# RTM_Connectors.net
KiCad netlist of a schematic drawn in Altium Designer
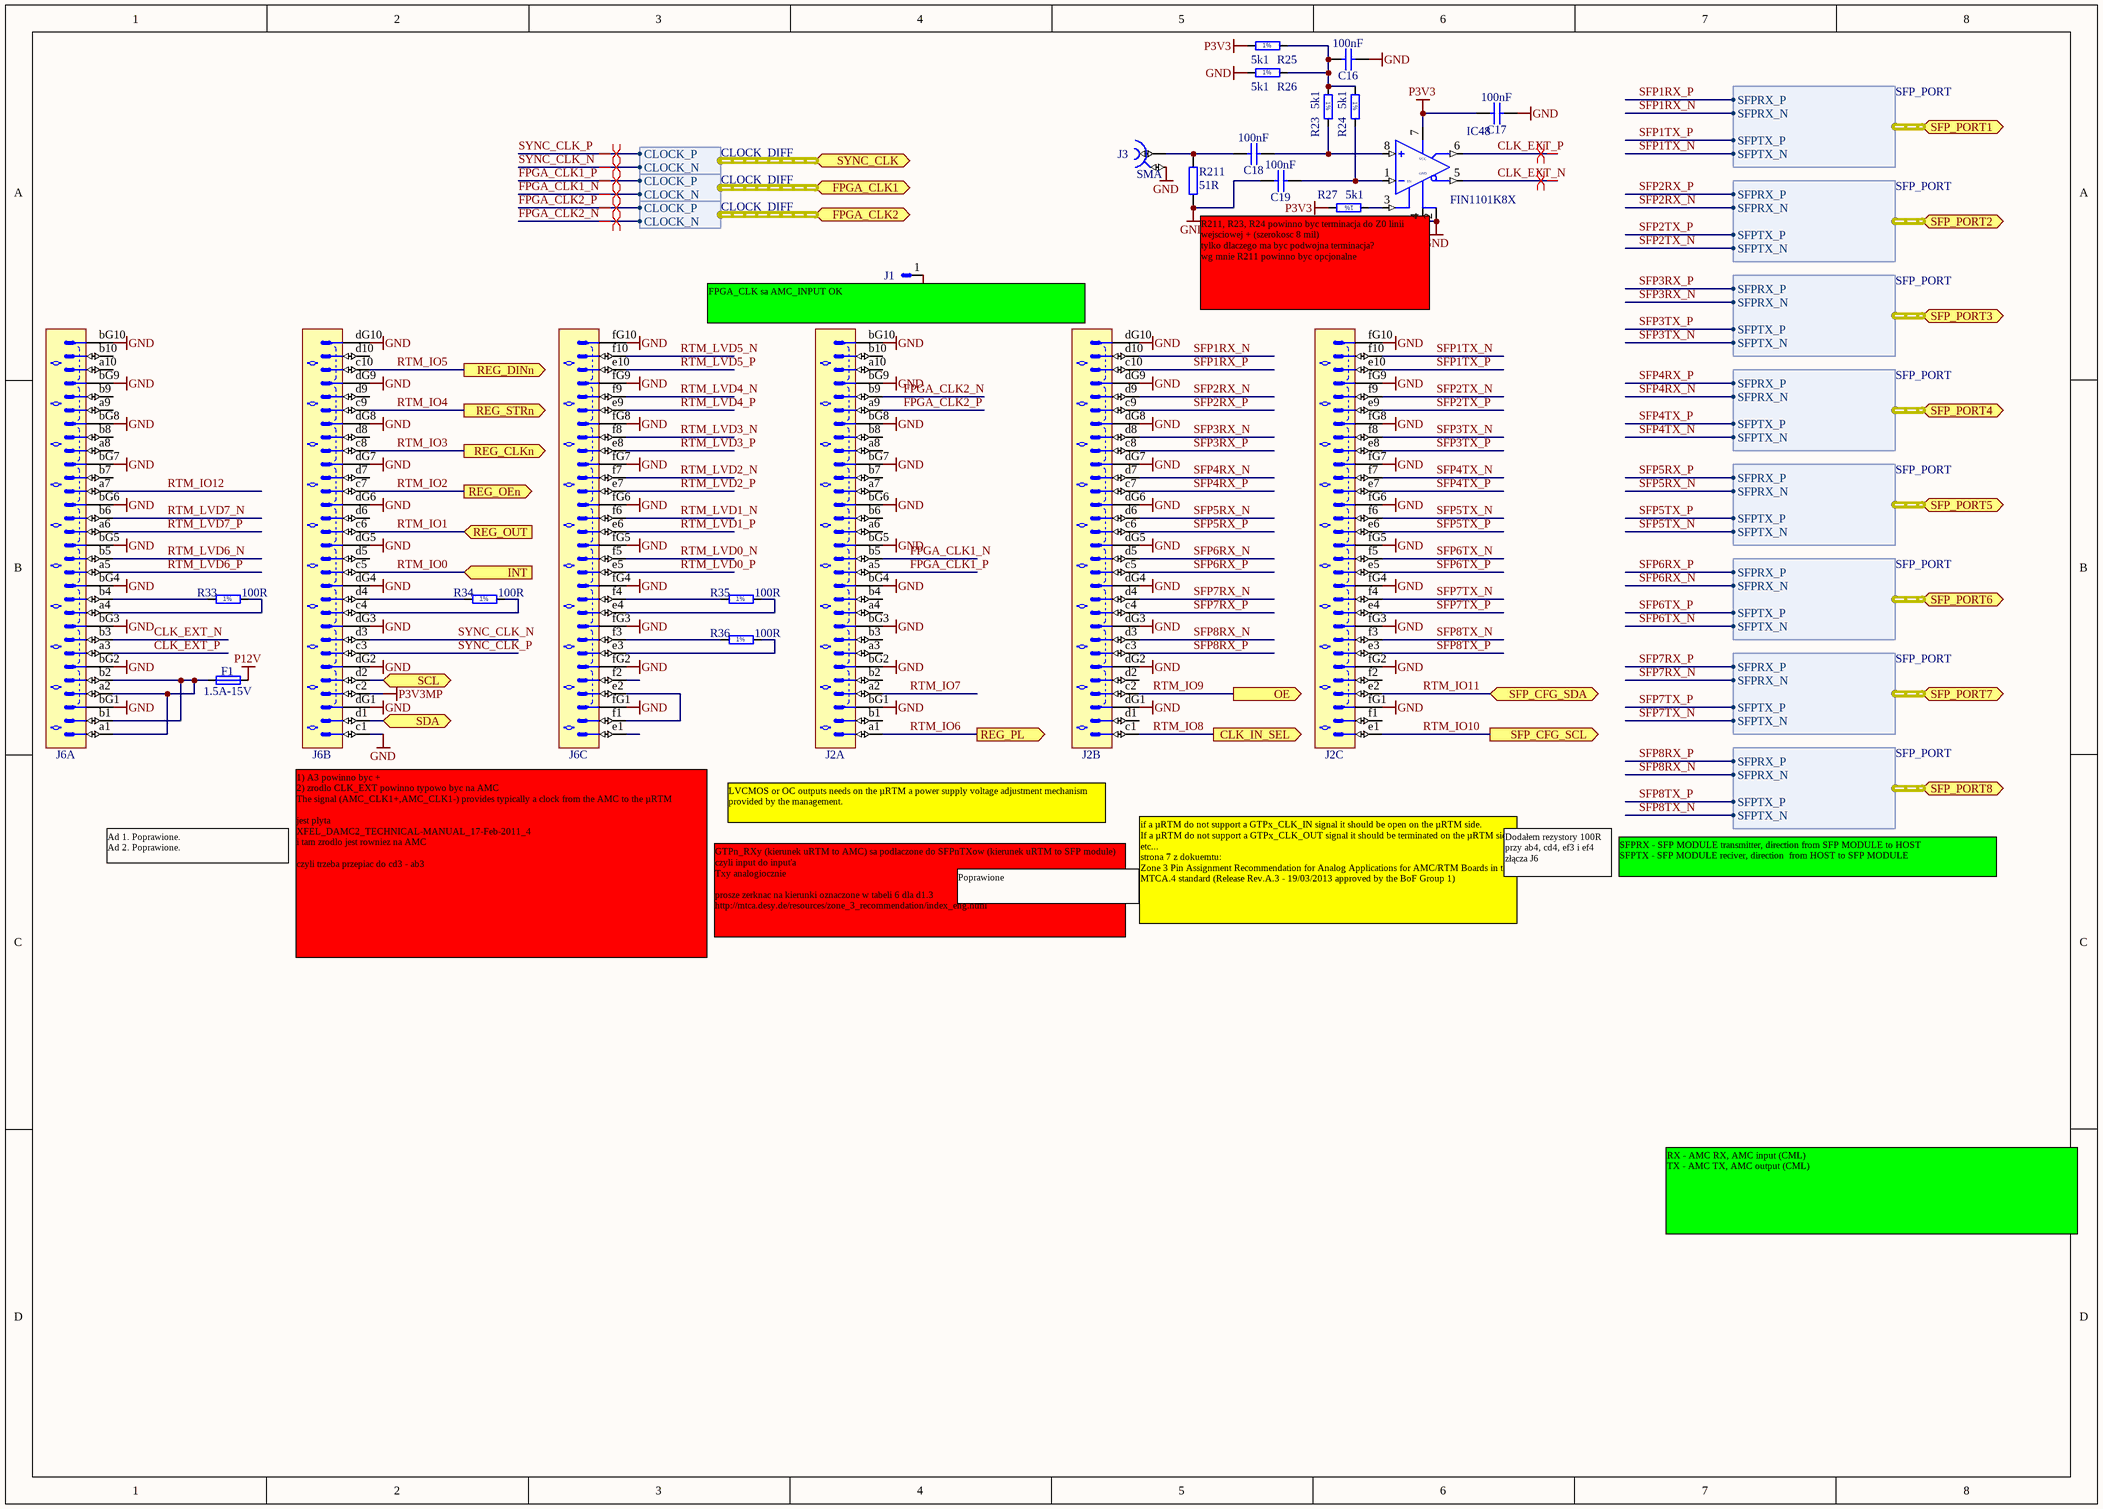
[diagram p0: RTM_Connectors.SchDoc]

(export (version "E")
  (design (tool "Eeschema 10.0.6"))
  (components
    (comp (ref "C16")
      (value "100nF")
      (footprint "CAPC1005X55N")
      (description "Non-polarised capacitor")
      (fields
        (field (name "PART NUMBER") "CC0402_100NF_16V_10%_X7R")
        (field (name "VOLTAGE") "16V")
        (field (name "AUTHOR") "CERN DEM JLC")
      )
      (libsource (lib "Capacitors") (part "Capacitor - non polarized"))
    )
    (comp (ref "C17")
      (value "100nF")
      (footprint "CAPC1005X55N")
      (description "Non-polarised capacitor")
      (fields
        (field (name "PART NUMBER") "CC0402_100NF_16V_10%_X7R")
        (field (name "VOLTAGE") "16V")
        (field (name "AUTHOR") "CERN DEM JLC")
      )
      (libsource (lib "Capacitors") (part "Capacitor - non polarized"))
    )
    (comp (ref "C18")
      (value "100nF")
      (footprint "CAPC1005X55N")
      (description "Non-polarised capacitor")
      (fields
        (field (name "PART NUMBER") "CC0402_100NF_16V_10%_X7R")
        (field (name "VOLTAGE") "16V")
        (field (name "AUTHOR") "CERN DEM JLC")
      )
      (libsource (lib "Capacitors") (part "Capacitor - non polarized"))
    )
    (comp (ref "C19")
      (value "100nF")
      (footprint "CAPC1005X55N")
      (description "Non-polarised capacitor")
      (fields
        (field (name "PART NUMBER") "CC0402_100NF_16V_10%_X7R")
        (field (name "VOLTAGE") "16V")
        (field (name "AUTHOR") "CERN DEM JLC")
      )
      (libsource (lib "Capacitors") (part "Capacitor - non polarized"))
    )
    (comp (ref "F1")
      (value "1.5A-15V")
      (footprint "FUSR_TYCO_SMD150F-2")
      (description "Fuse")
      (fields
        (field (name "PART NUMBER") "FUSR_TYCO_SMD150F-2")
        (field (name "MANUFACTURER") "TYCO ELECTRONICS")
        (field (name "AUTHOR") "CERN DEM JLC")
      )
      (libsource (lib "Eletro-mechanical") (part "Fuse"))
    )
    (comp (ref "IC48")
      (value "FIN1101K8X")
      (footprint "US8")
      (description "LVDS TO LVDS repeater3.3V")
      (libsource (lib "AMC_FMC_Carrier") (part "IFC_FIN1101K8X"))
    )
    (comp (ref "J1")
      (value "~")
      (footprint "TYCO_1469265-1")
      (description "Single Pin Male")
      (fields (field (name "PART NUMBER") "TYCO_1469265-1"))
      (libsource (lib "Connectors") (part "Single Pin Male"))
    )
    (comp (ref "J2")
      (value "~")
      (footprint "TYCO_6469183-1")
      (description "Connector 60 ATCA Male 30 Pairs (60 Signals) + 3x10 Ground")
      (fields (field (name "PART NUMBER") "TYCO_6469183-1"))
      (libsource (lib "Connectors") (part "Connector ATCA 60+30 Male"))
    )
    (comp (ref "J3")
      (value "SMA")
      (footprint "HUBER-SUHNER_85 SMA-50-0-101/111 NE")
      (fields
        (field (name "PART NUMBER") "HUBER-SUHNER_85_SMA-50-0-101/111_NE")
        (field (name "MANUFACTURER") "HUBER+SUHNER")
        (field (name "MANUFACTURER PART NUMBER") "85_SMA-50-0-101/111_NE")
        (field (name "AUTHOR") "CERN DEM JLC")
      )
      (libsource (lib "Connectors") (part "Coax_1Female_1Shield"))
    )
    (comp (ref "J6")
      (value "~")
      (footprint "TYCO_6469183-1")
      (description "Connector 60 ATCA Male 30 Pairs (60 Signals) + 3x10 Ground")
      (fields (field (name "PART NUMBER") "TYCO_6469183-1"))
      (libsource (lib "Connectors") (part "Connector ATCA 60+30 Male"))
    )
    (comp (ref "R23")
      (value "5k1")
      (footprint "RESC1608X55N")
      (description "Resistor - 1%")
      (fields
        (field (name "PART NUMBER") "R0603_5K1_1%_0.1W_100PPM")
        (field (name "POWER") "0.1W")
        (field (name "AUTHOR") "CERN DEM JLC")
      )
      (libsource (lib "Resistors") (part "Resistor - 1%"))
    )
    (comp (ref "R24")
      (value "5k1")
      (footprint "RESC1608X55N")
      (description "Resistor - 1%")
      (fields
        (field (name "PART NUMBER") "R0603_5K1_1%_0.1W_100PPM")
        (field (name "POWER") "0.1W")
        (field (name "AUTHOR") "CERN DEM JLC")
      )
      (libsource (lib "Resistors") (part "Resistor - 1%"))
    )
    (comp (ref "R25")
      (value "5k1")
      (footprint "RESC1608X55N")
      (description "Resistor - 1%")
      (fields
        (field (name "PART NUMBER") "R0603_5K1_1%_0.1W_100PPM")
        (field (name "POWER") "0.1W")
        (field (name "AUTHOR") "CERN DEM JLC")
      )
      (libsource (lib "Resistors") (part "Resistor - 1%"))
    )
    (comp (ref "R26")
      (value "5k1")
      (footprint "RESC1608X55N")
      (description "Resistor - 1%")
      (fields
        (field (name "PART NUMBER") "R0603_5K1_1%_0.1W_100PPM")
        (field (name "POWER") "0.1W")
        (field (name "AUTHOR") "CERN DEM JLC")
      )
      (libsource (lib "Resistors") (part "Resistor - 1%"))
    )
    (comp (ref "R27")
      (value "5k1")
      (footprint "RESC1608X55N")
      (description "Resistor - 1%")
      (fields
        (field (name "PART NUMBER") "R0603_5K1_1%_0.1W_100PPM")
        (field (name "POWER") "0.1W")
        (field (name "AUTHOR") "CERN DEM JLC")
      )
      (libsource (lib "Resistors") (part "Resistor - 1%"))
    )
    (comp (ref "R33")
      (value "100R")
      (footprint "RESC1608X55N")
      (description "Resistor - 1%")
      (fields
        (field (name "PART NUMBER") "R0603_5K1_1%_0.1W_100PPM")
        (field (name "POWER") "0.1W")
        (field (name "AUTHOR") "CERN DEM JLC")
      )
      (libsource (lib "Resistors") (part "Resistor - 1%"))
    )
    (comp (ref "R34")
      (value "100R")
      (footprint "RESC1608X55N")
      (description "Resistor - 1%")
      (fields
        (field (name "PART NUMBER") "R0603_5K1_1%_0.1W_100PPM")
        (field (name "POWER") "0.1W")
        (field (name "AUTHOR") "CERN DEM JLC")
      )
      (libsource (lib "Resistors") (part "Resistor - 1%"))
    )
    (comp (ref "R35")
      (value "100R")
      (footprint "RESC1608X55N")
      (description "Resistor - 1%")
      (fields
        (field (name "PART NUMBER") "R0603_5K1_1%_0.1W_100PPM")
        (field (name "POWER") "0.1W")
        (field (name "AUTHOR") "CERN DEM JLC")
      )
      (libsource (lib "Resistors") (part "Resistor - 1%"))
    )
    (comp (ref "R36")
      (value "100R")
      (footprint "RESC1608X55N")
      (description "Resistor - 1%")
      (fields
        (field (name "PART NUMBER") "R0603_5K1_1%_0.1W_100PPM")
        (field (name "POWER") "0.1W")
        (field (name "AUTHOR") "CERN DEM JLC")
      )
      (libsource (lib "Resistors") (part "Resistor - 1%"))
    )
    (comp (ref "R211")
      (value "51R")
      (footprint "0402R")
      (description "SMD Resistor")
      (libsource (lib "LIBRARY_SCH") (part "RES_0402"))
    )
  )
  (nets
    (net (code "3") (name "/CLK_EXT_N") (class "Default")
      (node (ref "IC48") (pin "5") (pinfunction "~{Q}_5") (pintype "output"))
      (node (ref "J6") (pin "b3") (pinfunction "b3_b3") (pintype "bidirectional"))
    )
    (net (code "4") (name "/CLK_EXT_P") (class "Default")
      (node (ref "IC48") (pin "6") (pinfunction "Q_6") (pintype "output"))
      (node (ref "J6") (pin "a3") (pinfunction "a3_a3") (pintype "bidirectional"))
    )
    (net (code "5") (name "/FPGA_CLK1_N") (class "Default")
      (node (ref "J2") (pin "b5") (pinfunction "b5_b5") (pintype "bidirectional"))
    )
    (net (code "6") (name "/FPGA_CLK1_P") (class "Default")
      (node (ref "J2") (pin "a5") (pinfunction "a5_a5") (pintype "bidirectional"))
    )
    (net (code "7") (name "/FPGA_CLK2_N") (class "Default")
      (node (ref "J2") (pin "b9") (pinfunction "b9_b9") (pintype "bidirectional"))
    )
    (net (code "8") (name "/FPGA_CLK2_P") (class "Default")
      (node (ref "J2") (pin "a9") (pinfunction "a9_a9") (pintype "bidirectional"))
    )
    (net (code "9") (name "/RTM_IO0") (class "Default")
      (node (ref "J6") (pin "c5") (pinfunction "c5_c5") (pintype "bidirectional"))
    )
    (net (code "10") (name "/RTM_IO1") (class "Default")
      (node (ref "J6") (pin "c6") (pinfunction "c6_c6") (pintype "bidirectional"))
    )
    (net (code "11") (name "/RTM_IO2") (class "Default")
      (node (ref "J6") (pin "c7") (pinfunction "c7_c7") (pintype "bidirectional"))
    )
    (net (code "12") (name "/RTM_IO3") (class "Default")
      (node (ref "J6") (pin "c8") (pinfunction "c8_c8") (pintype "bidirectional"))
    )
    (net (code "13") (name "/RTM_IO4") (class "Default")
      (node (ref "J6") (pin "c9") (pinfunction "c9_c9") (pintype "bidirectional"))
    )
    (net (code "14") (name "/RTM_IO5") (class "Default")
      (node (ref "J6") (pin "c10") (pinfunction "c10_c10") (pintype "bidirectional"))
    )
    (net (code "15") (name "/RTM_IO6") (class "Default")
      (node (ref "J2") (pin "a1") (pinfunction "a1_a1") (pintype "bidirectional"))
    )
    (net (code "16") (name "/RTM_IO7") (class "Default")
      (node (ref "J2") (pin "a2") (pinfunction "a2_a2") (pintype "bidirectional"))
    )
    (net (code "17") (name "/RTM_IO8") (class "Default")
      (node (ref "J2") (pin "c1") (pinfunction "c1_c1") (pintype "bidirectional"))
    )
    (net (code "18") (name "/RTM_IO9") (class "Default")
      (node (ref "J2") (pin "c2") (pinfunction "c2_c2") (pintype "bidirectional"))
    )
    (net (code "19") (name "/RTM_IO10") (class "Default")
      (node (ref "J2") (pin "e1") (pinfunction "e1_e1") (pintype "bidirectional"))
    )
    (net (code "20") (name "/RTM_IO11") (class "Default")
      (node (ref "J2") (pin "e2") (pinfunction "e2_e2") (pintype "bidirectional"))
    )
    (net (code "21") (name "/RTM_IO12") (class "Default")
      (node (ref "J6") (pin "a7") (pinfunction "a7_a7") (pintype "bidirectional"))
    )
    (net (code "22") (name "/RTM_LVD0_N") (class "Default")
      (node (ref "J6") (pin "f5") (pinfunction "f5_f5") (pintype "bidirectional"))
    )
    (net (code "23") (name "/RTM_LVD0_P") (class "Default")
      (node (ref "J6") (pin "e5") (pinfunction "e5_e5") (pintype "bidirectional"))
    )
    (net (code "24") (name "/RTM_LVD1_N") (class "Default")
      (node (ref "J6") (pin "f6") (pinfunction "f6_f6") (pintype "bidirectional"))
    )
    (net (code "25") (name "/RTM_LVD1_P") (class "Default")
      (node (ref "J6") (pin "e6") (pinfunction "e6_e6") (pintype "bidirectional"))
    )
    (net (code "26") (name "/RTM_LVD2_N") (class "Default")
      (node (ref "J6") (pin "f7") (pinfunction "f7_f7") (pintype "bidirectional"))
    )
    (net (code "27") (name "/RTM_LVD2_P") (class "Default")
      (node (ref "J6") (pin "e7") (pinfunction "e7_e7") (pintype "bidirectional"))
    )
    (net (code "28") (name "/RTM_LVD3_N") (class "Default")
      (node (ref "J6") (pin "f8") (pinfunction "f8_f8") (pintype "bidirectional"))
    )
    (net (code "29") (name "/RTM_LVD3_P") (class "Default")
      (node (ref "J6") (pin "e8") (pinfunction "e8_e8") (pintype "bidirectional"))
    )
    (net (code "30") (name "/RTM_LVD4_N") (class "Default")
      (node (ref "J6") (pin "f9") (pinfunction "f9_f9") (pintype "bidirectional"))
    )
    (net (code "31") (name "/RTM_LVD4_P") (class "Default")
      (node (ref "J6") (pin "e9") (pinfunction "e9_e9") (pintype "bidirectional"))
    )
    (net (code "32") (name "/RTM_LVD5_N") (class "Default")
      (node (ref "J6") (pin "f10") (pinfunction "f10_f10") (pintype "bidirectional"))
    )
    (net (code "33") (name "/RTM_LVD5_P") (class "Default")
      (node (ref "J6") (pin "e10") (pinfunction "e10_e10") (pintype "bidirectional"))
    )
    (net (code "34") (name "/RTM_LVD6_N") (class "Default")
      (node (ref "J6") (pin "b5") (pinfunction "b5_b5") (pintype "bidirectional"))
    )
    (net (code "35") (name "/RTM_LVD6_P") (class "Default")
      (node (ref "J6") (pin "a5") (pinfunction "a5_a5") (pintype "bidirectional"))
    )
    (net (code "36") (name "/RTM_LVD7_N") (class "Default")
      (node (ref "J6") (pin "b6") (pinfunction "b6_b6") (pintype "bidirectional"))
    )
    (net (code "37") (name "/RTM_LVD7_P") (class "Default")
      (node (ref "J6") (pin "a6") (pinfunction "a6_a6") (pintype "bidirectional"))
    )
    (net (code "38") (name "/SCL") (class "Default")
      (node (ref "J6") (pin "d2") (pinfunction "d2_d2") (pintype "bidirectional"))
    )
    (net (code "39") (name "/SDA") (class "Default")
      (node (ref "J6") (pin "d1") (pinfunction "d1_d1") (pintype "bidirectional"))
    )
    (net (code "40") (name "/SFP1RX_N") (class "Default")
      (node (ref "J2") (pin "d10") (pinfunction "d10_d10") (pintype "bidirectional"))
    )
    (net (code "41") (name "/SFP1RX_P") (class "Default")
      (node (ref "J2") (pin "c10") (pinfunction "c10_c10") (pintype "bidirectional"))
    )
    (net (code "42") (name "/SFP1TX_N") (class "Default")
      (node (ref "J2") (pin "f10") (pinfunction "f10_f10") (pintype "bidirectional"))
    )
    (net (code "43") (name "/SFP1TX_P") (class "Default")
      (node (ref "J2") (pin "e10") (pinfunction "e10_e10") (pintype "bidirectional"))
    )
    (net (code "44") (name "/SFP2RX_N") (class "Default")
      (node (ref "J2") (pin "d9") (pinfunction "d9_d9") (pintype "bidirectional"))
    )
    (net (code "45") (name "/SFP2RX_P") (class "Default")
      (node (ref "J2") (pin "c9") (pinfunction "c9_c9") (pintype "bidirectional"))
    )
    (net (code "46") (name "/SFP2TX_N") (class "Default")
      (node (ref "J2") (pin "f9") (pinfunction "f9_f9") (pintype "bidirectional"))
    )
    (net (code "47") (name "/SFP2TX_P") (class "Default")
      (node (ref "J2") (pin "e9") (pinfunction "e9_e9") (pintype "bidirectional"))
    )
    (net (code "48") (name "/SFP3RX_N") (class "Default")
      (node (ref "J2") (pin "d8") (pinfunction "d8_d8") (pintype "bidirectional"))
    )
    (net (code "49") (name "/SFP3RX_P") (class "Default")
      (node (ref "J2") (pin "c8") (pinfunction "c8_c8") (pintype "bidirectional"))
    )
    (net (code "50") (name "/SFP3TX_N") (class "Default")
      (node (ref "J2") (pin "f8") (pinfunction "f8_f8") (pintype "bidirectional"))
    )
    (net (code "51") (name "/SFP3TX_P") (class "Default")
      (node (ref "J2") (pin "e8") (pinfunction "e8_e8") (pintype "bidirectional"))
    )
    (net (code "52") (name "/SFP4RX_N") (class "Default")
      (node (ref "J2") (pin "d7") (pinfunction "d7_d7") (pintype "bidirectional"))
    )
    (net (code "53") (name "/SFP4RX_P") (class "Default")
      (node (ref "J2") (pin "c7") (pinfunction "c7_c7") (pintype "bidirectional"))
    )
    (net (code "54") (name "/SFP4TX_N") (class "Default")
      (node (ref "J2") (pin "f7") (pinfunction "f7_f7") (pintype "bidirectional"))
    )
    (net (code "55") (name "/SFP4TX_P") (class "Default")
      (node (ref "J2") (pin "e7") (pinfunction "e7_e7") (pintype "bidirectional"))
    )
    (net (code "56") (name "/SFP5RX_N") (class "Default")
      (node (ref "J2") (pin "d6") (pinfunction "d6_d6") (pintype "bidirectional"))
    )
    (net (code "57") (name "/SFP5RX_P") (class "Default")
      (node (ref "J2") (pin "c6") (pinfunction "c6_c6") (pintype "bidirectional"))
    )
    (net (code "58") (name "/SFP5TX_N") (class "Default")
      (node (ref "J2") (pin "f6") (pinfunction "f6_f6") (pintype "bidirectional"))
    )
    (net (code "59") (name "/SFP5TX_P") (class "Default")
      (node (ref "J2") (pin "e6") (pinfunction "e6_e6") (pintype "bidirectional"))
    )
    (net (code "60") (name "/SFP6RX_N") (class "Default")
      (node (ref "J2") (pin "d5") (pinfunction "d5_d5") (pintype "bidirectional"))
    )
    (net (code "61") (name "/SFP6RX_P") (class "Default")
      (node (ref "J2") (pin "c5") (pinfunction "c5_c5") (pintype "bidirectional"))
    )
    (net (code "62") (name "/SFP6TX_N") (class "Default")
      (node (ref "J2") (pin "f5") (pinfunction "f5_f5") (pintype "bidirectional"))
    )
    (net (code "63") (name "/SFP6TX_P") (class "Default")
      (node (ref "J2") (pin "e5") (pinfunction "e5_e5") (pintype "bidirectional"))
    )
    (net (code "64") (name "/SFP7RX_N") (class "Default")
      (node (ref "J2") (pin "d4") (pinfunction "d4_d4") (pintype "bidirectional"))
    )
    (net (code "65") (name "/SFP7RX_P") (class "Default")
      (node (ref "J2") (pin "c4") (pinfunction "c4_c4") (pintype "bidirectional"))
    )
    (net (code "66") (name "/SFP7TX_N") (class "Default")
      (node (ref "J2") (pin "f4") (pinfunction "f4_f4") (pintype "bidirectional"))
    )
    (net (code "67") (name "/SFP7TX_P") (class "Default")
      (node (ref "J2") (pin "e4") (pinfunction "e4_e4") (pintype "bidirectional"))
    )
    (net (code "68") (name "/SFP8RX_N") (class "Default")
      (node (ref "J2") (pin "d3") (pinfunction "d3_d3") (pintype "bidirectional"))
    )
    (net (code "69") (name "/SFP8RX_P") (class "Default")
      (node (ref "J2") (pin "c3") (pinfunction "c3_c3") (pintype "bidirectional"))
    )
    (net (code "70") (name "/SFP8TX_N") (class "Default")
      (node (ref "J2") (pin "f3") (pinfunction "f3_f3") (pintype "bidirectional"))
    )
    (net (code "71") (name "/SFP8TX_P") (class "Default")
      (node (ref "J2") (pin "e3") (pinfunction "e3_e3") (pintype "bidirectional"))
    )
    (net (code "72") (name "/SYNC_CLK_N") (class "Default")
      (node (ref "J6") (pin "d3") (pinfunction "d3_d3") (pintype "bidirectional"))
    )
    (net (code "73") (name "/SYNC_CLK_P") (class "Default")
      (node (ref "J6") (pin "c3") (pinfunction "c3_c3") (pintype "bidirectional"))
    )
    (net (code "76") (name "GND") (class "Default")
      (node (ref "C16") (pin "2") (pinfunction "2_2") (pintype "passive"))
      (node (ref "C17") (pin "2") (pinfunction "2_2") (pintype "passive"))
      (node (ref "C19") (pin "1") (pinfunction "1_1") (pintype "passive"))
      (node (ref "IC48") (pin "2") (pinfunction "GND_2") (pintype "power_in"))
      (node (ref "IC48") (pin "4") (pinfunction "GND_4") (pintype "power_in"))
      (node (ref "J1") (pin "1") (pinfunction "1_1") (pintype "bidirectional"))
      (node (ref "J2") (pin "bG1") (pinfunction "bG1_bG1") (pintype "power_in"))
      (node (ref "J2") (pin "bG10") (pinfunction "bG10_bG10") (pintype "power_in"))
      (node (ref "J2") (pin "bG2") (pinfunction "bG2_bG2") (pintype "power_in"))
      (node (ref "J2") (pin "bG3") (pinfunction "bG3_bG3") (pintype "power_in"))
      (node (ref "J2") (pin "bG4") (pinfunction "bG4_bG4") (pintype "power_in"))
      (node (ref "J2") (pin "bG5") (pinfunction "bG5_bG5") (pintype "power_in"))
      (node (ref "J2") (pin "bG6") (pinfunction "bG6_bG6") (pintype "power_in"))
      (node (ref "J2") (pin "bG7") (pinfunction "bG7_bG7") (pintype "power_in"))
      (node (ref "J2") (pin "bG8") (pinfunction "bG8_bG8") (pintype "power_in"))
      (node (ref "J2") (pin "bG9") (pinfunction "bG9_bG9") (pintype "power_in"))
      (node (ref "J2") (pin "dG1") (pinfunction "dG1_dG1") (pintype "power_in"))
      (node (ref "J2") (pin "dG10") (pinfunction "dG10_dG10") (pintype "power_in"))
      (node (ref "J2") (pin "dG2") (pinfunction "dG2_dG2") (pintype "power_in"))
      (node (ref "J2") (pin "dG3") (pinfunction "dG3_dG3") (pintype "power_in"))
      (node (ref "J2") (pin "dG4") (pinfunction "dG4_dG4") (pintype "power_in"))
      (node (ref "J2") (pin "dG5") (pinfunction "dG5_dG5") (pintype "power_in"))
      (node (ref "J2") (pin "dG6") (pinfunction "dG6_dG6") (pintype "power_in"))
      (node (ref "J2") (pin "dG7") (pinfunction "dG7_dG7") (pintype "power_in"))
      (node (ref "J2") (pin "dG8") (pinfunction "dG8_dG8") (pintype "power_in"))
      (node (ref "J2") (pin "dG9") (pinfunction "dG9_dG9") (pintype "power_in"))
      (node (ref "J2") (pin "fG1") (pinfunction "fG1_fG1") (pintype "power_in"))
      (node (ref "J2") (pin "fG10") (pinfunction "fG10_fG10") (pintype "power_in"))
      (node (ref "J2") (pin "fG2") (pinfunction "fG2_fG2") (pintype "power_in"))
      (node (ref "J2") (pin "fG3") (pinfunction "fG3_fG3") (pintype "power_in"))
      (node (ref "J2") (pin "fG4") (pinfunction "fG4_fG4") (pintype "power_in"))
      (node (ref "J2") (pin "fG5") (pinfunction "fG5_fG5") (pintype "power_in"))
      (node (ref "J2") (pin "fG6") (pinfunction "fG6_fG6") (pintype "power_in"))
      (node (ref "J2") (pin "fG7") (pinfunction "fG7_fG7") (pintype "power_in"))
      (node (ref "J2") (pin "fG8") (pinfunction "fG8_fG8") (pintype "power_in"))
      (node (ref "J2") (pin "fG9") (pinfunction "fG9_fG9") (pintype "power_in"))
      (node (ref "J3") (pin "2") (pinfunction "2_2") (pintype "bidirectional"))
      (node (ref "J6") (pin "bG1") (pinfunction "bG1_bG1") (pintype "power_in"))
      (node (ref "J6") (pin "bG10") (pinfunction "bG10_bG10") (pintype "power_in"))
      (node (ref "J6") (pin "bG2") (pinfunction "bG2_bG2") (pintype "power_in"))
      (node (ref "J6") (pin "bG3") (pinfunction "bG3_bG3") (pintype "power_in"))
      (node (ref "J6") (pin "bG4") (pinfunction "bG4_bG4") (pintype "power_in"))
      (node (ref "J6") (pin "bG5") (pinfunction "bG5_bG5") (pintype "power_in"))
      (node (ref "J6") (pin "bG6") (pinfunction "bG6_bG6") (pintype "power_in"))
      (node (ref "J6") (pin "bG7") (pinfunction "bG7_bG7") (pintype "power_in"))
      (node (ref "J6") (pin "bG8") (pinfunction "bG8_bG8") (pintype "power_in"))
      (node (ref "J6") (pin "bG9") (pinfunction "bG9_bG9") (pintype "power_in"))
      (node (ref "J6") (pin "c1") (pinfunction "c1_c1") (pintype "bidirectional"))
      (node (ref "J6") (pin "dG1") (pinfunction "dG1_dG1") (pintype "power_in"))
      (node (ref "J6") (pin "dG10") (pinfunction "dG10_dG10") (pintype "power_in"))
      (node (ref "J6") (pin "dG2") (pinfunction "dG2_dG2") (pintype "power_in"))
      (node (ref "J6") (pin "dG3") (pinfunction "dG3_dG3") (pintype "power_in"))
      (node (ref "J6") (pin "dG4") (pinfunction "dG4_dG4") (pintype "power_in"))
      (node (ref "J6") (pin "dG5") (pinfunction "dG5_dG5") (pintype "power_in"))
      (node (ref "J6") (pin "dG6") (pinfunction "dG6_dG6") (pintype "power_in"))
      (node (ref "J6") (pin "dG7") (pinfunction "dG7_dG7") (pintype "power_in"))
      (node (ref "J6") (pin "dG8") (pinfunction "dG8_dG8") (pintype "power_in"))
      (node (ref "J6") (pin "dG9") (pinfunction "dG9_dG9") (pintype "power_in"))
      (node (ref "J6") (pin "fG1") (pinfunction "fG1_fG1") (pintype "power_in"))
      (node (ref "J6") (pin "fG10") (pinfunction "fG10_fG10") (pintype "power_in"))
      (node (ref "J6") (pin "fG2") (pinfunction "fG2_fG2") (pintype "power_in"))
      (node (ref "J6") (pin "fG3") (pinfunction "fG3_fG3") (pintype "power_in"))
      (node (ref "J6") (pin "fG4") (pinfunction "fG4_fG4") (pintype "power_in"))
      (node (ref "J6") (pin "fG5") (pinfunction "fG5_fG5") (pintype "power_in"))
      (node (ref "J6") (pin "fG6") (pinfunction "fG6_fG6") (pintype "power_in"))
      (node (ref "J6") (pin "fG7") (pinfunction "fG7_fG7") (pintype "power_in"))
      (node (ref "J6") (pin "fG8") (pinfunction "fG8_fG8") (pintype "power_in"))
      (node (ref "J6") (pin "fG9") (pinfunction "fG9_fG9") (pintype "power_in"))
      (node (ref "R211") (pin "2") (pinfunction "2_2") (pintype "passive"))
      (node (ref "R26") (pin "1") (pinfunction "1_1") (pintype "passive"))
    )
    (net (code "77") (name "Net-(C16-Pad1)") (class "Default")
      (node (ref "C16") (pin "1") (pinfunction "1_1") (pintype "passive"))
      (node (ref "R23") (pin "1") (pinfunction "1_1") (pintype "passive"))
      (node (ref "R24") (pin "1") (pinfunction "1_1") (pintype "passive"))
      (node (ref "R25") (pin "2") (pinfunction "2_2") (pintype "passive"))
      (node (ref "R26") (pin "2") (pinfunction "2_2") (pintype "passive"))
    )
    (net (code "78") (name "Net-(C18-Pad1)") (class "Default")
      (node (ref "C18") (pin "1") (pinfunction "1_1") (pintype "passive"))
      (node (ref "J3") (pin "1") (pinfunction "1_1") (pintype "bidirectional"))
      (node (ref "R211") (pin "1") (pinfunction "1_1") (pintype "passive"))
    )
    (net (code "79") (name "Net-(C18-Pad2)") (class "Default")
      (node (ref "C18") (pin "2") (pinfunction "2_2") (pintype "passive"))
      (node (ref "IC48") (pin "8") (pinfunction "IN_8") (pintype "input"))
      (node (ref "R23") (pin "2") (pinfunction "2_2") (pintype "passive"))
    )
    (net (code "80") (name "Net-(C19-Pad2)") (class "Default")
      (node (ref "C19") (pin "2") (pinfunction "2_2") (pintype "passive"))
      (node (ref "IC48") (pin "1") (pinfunction "IN_1") (pintype "input"))
      (node (ref "R24") (pin "2") (pinfunction "2_2") (pintype "passive"))
    )
    (net (code "81") (name "Net-(F1-Pad1)") (class "Default")
      (node (ref "F1") (pin "1") (pinfunction "1_1") (pintype "passive"))
      (node (ref "J6") (pin "a1") (pinfunction "a1_a1") (pintype "bidirectional"))
      (node (ref "J6") (pin "a2") (pinfunction "a2_a2") (pintype "bidirectional"))
      (node (ref "J6") (pin "b1") (pinfunction "b1_b1") (pintype "bidirectional"))
      (node (ref "J6") (pin "b2") (pinfunction "b2_b2") (pintype "bidirectional"))
    )
    (net (code "82") (name "Net-(IC48-EN)") (class "Default")
      (node (ref "IC48") (pin "3") (pinfunction "EN_3") (pintype "input"))
      (node (ref "R27") (pin "1") (pinfunction "1_1") (pintype "passive"))
    )
    (net (code "83") (name "Net-(J6-Pada4)") (class "Default")
      (node (ref "J6") (pin "a4") (pinfunction "a4_a4") (pintype "bidirectional"))
      (node (ref "R33") (pin "2") (pinfunction "2_2") (pintype "passive"))
    )
    (net (code "84") (name "Net-(J6-Padb4)") (class "Default")
      (node (ref "J6") (pin "b4") (pinfunction "b4_b4") (pintype "bidirectional"))
      (node (ref "R33") (pin "1") (pinfunction "1_1") (pintype "passive"))
    )
    (net (code "85") (name "Net-(J6-Padc4)") (class "Default")
      (node (ref "J6") (pin "c4") (pinfunction "c4_c4") (pintype "bidirectional"))
      (node (ref "R34") (pin "2") (pinfunction "2_2") (pintype "passive"))
    )
    (net (code "86") (name "Net-(J6-Padd4)") (class "Default")
      (node (ref "J6") (pin "d4") (pinfunction "d4_d4") (pintype "bidirectional"))
      (node (ref "R34") (pin "1") (pinfunction "1_1") (pintype "passive"))
    )
    (net (code "87") (name "Net-(J6-Pade2)") (class "Default")
      (node (ref "J6") (pin "e2") (pinfunction "e2_e2") (pintype "bidirectional"))
      (node (ref "J6") (pin "f1") (pinfunction "f1_f1") (pintype "bidirectional"))
    )
    (net (code "88") (name "Net-(J6-Pade3)") (class "Default")
      (node (ref "J6") (pin "e3") (pinfunction "e3_e3") (pintype "bidirectional"))
      (node (ref "R36") (pin "2") (pinfunction "2_2") (pintype "passive"))
    )
    (net (code "89") (name "Net-(J6-Pade4)") (class "Default")
      (node (ref "J6") (pin "e4") (pinfunction "e4_e4") (pintype "bidirectional"))
      (node (ref "R35") (pin "2") (pinfunction "2_2") (pintype "passive"))
    )
    (net (code "90") (name "Net-(J6-Padf3)") (class "Default")
      (node (ref "J6") (pin "f3") (pinfunction "f3_f3") (pintype "bidirectional"))
      (node (ref "R36") (pin "1") (pinfunction "1_1") (pintype "passive"))
    )
    (net (code "91") (name "Net-(J6-Padf4)") (class "Default")
      (node (ref "J6") (pin "f4") (pinfunction "f4_f4") (pintype "bidirectional"))
      (node (ref "R35") (pin "1") (pinfunction "1_1") (pintype "passive"))
    )
    (net (code "92") (name "P3V3") (class "Default")
      (node (ref "C17") (pin "1") (pinfunction "1_1") (pintype "passive"))
      (node (ref "IC48") (pin "7") (pinfunction "VCC_7") (pintype "power_in"))
      (node (ref "R25") (pin "1") (pinfunction "1_1") (pintype "passive"))
      (node (ref "R27") (pin "2") (pinfunction "2_2") (pintype "passive"))
    )
    (net (code "93") (name "P3V3MP") (class "Default")
      (node (ref "J6") (pin "c2") (pinfunction "c2_c2") (pintype "bidirectional"))
    )
    (net (code "94") (name "P12V") (class "Default")
      (node (ref "F1") (pin "2") (pinfunction "2_2") (pintype "passive"))
    )
    (net (code "95") (name "unconnected-(J2-Pada3)") (class "Default")
      (node (ref "J2") (pin "a3") (pinfunction "a3_a3") (pintype "bidirectional"))
    )
    (net (code "96") (name "unconnected-(J2-Pada4)") (class "Default")
      (node (ref "J2") (pin "a4") (pinfunction "a4_a4") (pintype "bidirectional"))
    )
    (net (code "97") (name "unconnected-(J2-Pada6)") (class "Default")
      (node (ref "J2") (pin "a6") (pinfunction "a6_a6") (pintype "bidirectional"))
    )
    (net (code "98") (name "unconnected-(J2-Pada7)") (class "Default")
      (node (ref "J2") (pin "a7") (pinfunction "a7_a7") (pintype "bidirectional"))
    )
    (net (code "99") (name "unconnected-(J2-Pada8)") (class "Default")
      (node (ref "J2") (pin "a8") (pinfunction "a8_a8") (pintype "bidirectional"))
    )
    (net (code "100") (name "unconnected-(J2-Pada10)") (class "Default")
      (node (ref "J2") (pin "a10") (pinfunction "a10_a10") (pintype "bidirectional"))
    )
    (net (code "101") (name "unconnected-(J2-Padb1)") (class "Default")
      (node (ref "J2") (pin "b1") (pinfunction "b1_b1") (pintype "bidirectional"))
    )
    (net (code "102") (name "unconnected-(J2-Padb2)") (class "Default")
      (node (ref "J2") (pin "b2") (pinfunction "b2_b2") (pintype "bidirectional"))
    )
    (net (code "103") (name "unconnected-(J2-Padb3)") (class "Default")
      (node (ref "J2") (pin "b3") (pinfunction "b3_b3") (pintype "bidirectional"))
    )
    (net (code "104") (name "unconnected-(J2-Padb4)") (class "Default")
      (node (ref "J2") (pin "b4") (pinfunction "b4_b4") (pintype "bidirectional"))
    )
    (net (code "105") (name "unconnected-(J2-Padb6)") (class "Default")
      (node (ref "J2") (pin "b6") (pinfunction "b6_b6") (pintype "bidirectional"))
    )
    (net (code "106") (name "unconnected-(J2-Padb7)") (class "Default")
      (node (ref "J2") (pin "b7") (pinfunction "b7_b7") (pintype "bidirectional"))
    )
    (net (code "107") (name "unconnected-(J2-Padb8)") (class "Default")
      (node (ref "J2") (pin "b8") (pinfunction "b8_b8") (pintype "bidirectional"))
    )
    (net (code "108") (name "unconnected-(J2-Padb10)") (class "Default")
      (node (ref "J2") (pin "b10") (pinfunction "b10_b10") (pintype "bidirectional"))
    )
    (net (code "109") (name "unconnected-(J2-Padd1)") (class "Default")
      (node (ref "J2") (pin "d1") (pinfunction "d1_d1") (pintype "bidirectional"))
    )
    (net (code "110") (name "unconnected-(J2-Padd2)") (class "Default")
      (node (ref "J2") (pin "d2") (pinfunction "d2_d2") (pintype "bidirectional"))
    )
    (net (code "111") (name "unconnected-(J2-Padf1)") (class "Default")
      (node (ref "J2") (pin "f1") (pinfunction "f1_f1") (pintype "bidirectional"))
    )
    (net (code "112") (name "unconnected-(J2-Padf2)") (class "Default")
      (node (ref "J2") (pin "f2") (pinfunction "f2_f2") (pintype "bidirectional"))
    )
    (net (code "113") (name "unconnected-(J6-Pada8)") (class "Default")
      (node (ref "J6") (pin "a8") (pinfunction "a8_a8") (pintype "bidirectional"))
    )
    (net (code "114") (name "unconnected-(J6-Pada9)") (class "Default")
      (node (ref "J6") (pin "a9") (pinfunction "a9_a9") (pintype "bidirectional"))
    )
    (net (code "115") (name "unconnected-(J6-Pada10)") (class "Default")
      (node (ref "J6") (pin "a10") (pinfunction "a10_a10") (pintype "bidirectional"))
    )
    (net (code "116") (name "unconnected-(J6-Padb7)") (class "Default")
      (node (ref "J6") (pin "b7") (pinfunction "b7_b7") (pintype "bidirectional"))
    )
    (net (code "117") (name "unconnected-(J6-Padb8)") (class "Default")
      (node (ref "J6") (pin "b8") (pinfunction "b8_b8") (pintype "bidirectional"))
    )
    (net (code "118") (name "unconnected-(J6-Padb9)") (class "Default")
      (node (ref "J6") (pin "b9") (pinfunction "b9_b9") (pintype "bidirectional"))
    )
    (net (code "119") (name "unconnected-(J6-Padb10)") (class "Default")
      (node (ref "J6") (pin "b10") (pinfunction "b10_b10") (pintype "bidirectional"))
    )
    (net (code "120") (name "unconnected-(J6-Padd5)") (class "Default")
      (node (ref "J6") (pin "d5") (pinfunction "d5_d5") (pintype "bidirectional"))
    )
    (net (code "121") (name "unconnected-(J6-Padd6)") (class "Default")
      (node (ref "J6") (pin "d6") (pinfunction "d6_d6") (pintype "bidirectional"))
    )
    (net (code "122") (name "unconnected-(J6-Padd7)") (class "Default")
      (node (ref "J6") (pin "d7") (pinfunction "d7_d7") (pintype "bidirectional"))
    )
    (net (code "123") (name "unconnected-(J6-Padd8)") (class "Default")
      (node (ref "J6") (pin "d8") (pinfunction "d8_d8") (pintype "bidirectional"))
    )
    (net (code "124") (name "unconnected-(J6-Padd9)") (class "Default")
      (node (ref "J6") (pin "d9") (pinfunction "d9_d9") (pintype "bidirectional"))
    )
    (net (code "125") (name "unconnected-(J6-Padd10)") (class "Default")
      (node (ref "J6") (pin "d10") (pinfunction "d10_d10") (pintype "bidirectional"))
    )
    (net (code "126") (name "unconnected-(J6-Pade1)") (class "Default")
      (node (ref "J6") (pin "e1") (pinfunction "e1_e1") (pintype "bidirectional"))
    )
    (net (code "127") (name "unconnected-(J6-Padf2)") (class "Default")
      (node (ref "J6") (pin "f2") (pinfunction "f2_f2") (pintype "bidirectional"))
    )
  )
)
